# E-Fuse.net
KiCad netlist of a schematic drawn in Altium Designer
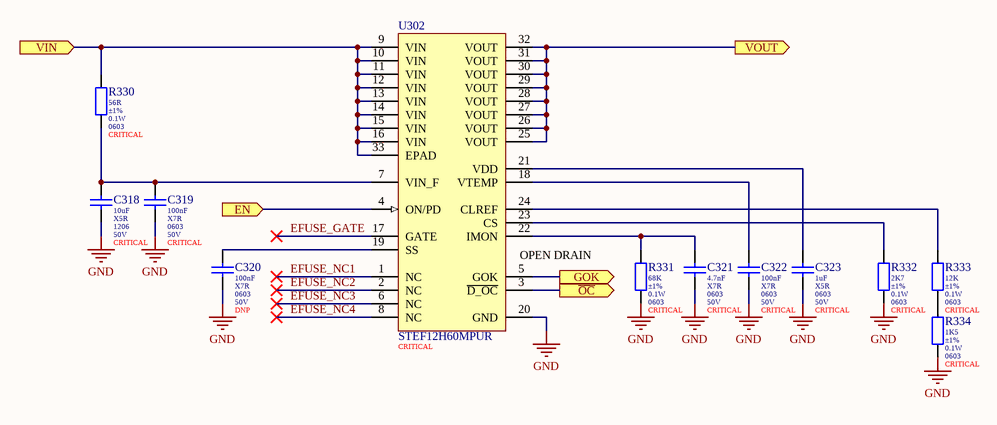
[diagram p0: E-Fuse.SchDoc]

(export (version "E")
  (design (tool "Eeschema 10.0.6"))
  (components
    (comp (ref "C318")
      (value "10uF")
      (footprint "1206_160_H (Samsumg) B")
      (description "MLCC 10uF 1206 50V X5R ±10%")
      (fields
        (field (name "DIELECTRIC") "X5R")
        (field (name "PACKAGE") "1206")
        (field (name "VOLTAGE") "50V")
        (field (name "POPULATE") "CRITICAL")
        (field (name "LCSC PART NUMBER") "C13585")
        (field (name "MANUFACTURER") "Samsung")
      )
      (libsource (lib "University of Cape Town") (part "Symbol"))
    )
    (comp (ref "C319")
      (value "100nF")
      (footprint "0603 (Yageo DA) B")
      (description "MLCC 100nF 50V 0603 X7R ±10%")
      (fields
        (field (name "DIELECTRIC") "X7R")
        (field (name "PACKAGE") "0603")
        (field (name "VOLTAGE") "50V")
        (field (name "POPULATE") "CRITICAL")
        (field (name "LCSC PART NUMBER") "C14663")
        (field (name "TOLERANCE") "±10%")
      )
      (libsource (lib "University of Cape Town") (part "Symbol"))
    )
    (comp (ref "C320")
      (value "100nF")
      (footprint "0603 (Yageo DA) B")
      (description "MLCC 100nF 50V 0603 X7R ±10%")
      (fields
        (field (name "DIELECTRIC") "X7R")
        (field (name "PACKAGE") "0603")
        (field (name "VOLTAGE") "50V")
        (field (name "POPULATE") "DNP")
        (field (name "LCSC PART NUMBER") "C14663")
        (field (name "TOLERANCE") "±10%")
      )
      (libsource (lib "University of Cape Town") (part "Symbol"))
    )
    (comp (ref "C321")
      (value "4.7nF")
      (footprint "0603_080 (Guandong) B")
      (description "MLCC 4.7nF 0603 50V X7R ±10%")
      (fields
        (field (name "DIELECTRIC") "X7R")
        (field (name "PACKAGE") "0603")
        (field (name "VOLTAGE") "50V")
        (field (name "POPULATE") "CRITICAL")
        (field (name "LCSC PART NUMBER") "C53987")
        (field (name "TOLERANCE") "±15%")
      )
      (libsource (lib "University of Cape Town") (part "Symbol"))
    )
    (comp (ref "C322")
      (value "100nF")
      (footprint "0603 (Yageo DA) B")
      (description "MLCC 100nF 50V 0603 X7R ±10%")
      (fields
        (field (name "DIELECTRIC") "X7R")
        (field (name "PACKAGE") "0603")
        (field (name "VOLTAGE") "50V")
        (field (name "POPULATE") "CRITICAL")
        (field (name "LCSC PART NUMBER") "C14663")
        (field (name "TOLERANCE") "±10%")
      )
      (libsource (lib "University of Cape Town") (part "Symbol"))
    )
    (comp (ref "C323")
      (value "1uF")
      (footprint "0603_080_8 (Samsung) B")
      (description "MLCC 1uF 0603 50V X5R ±10%")
      (fields
        (field (name "DIELECTRIC") "X5R")
        (field (name "PACKAGE") "0603")
        (field (name "VOLTAGE") "50V")
        (field (name "POPULATE") "CRITICAL")
        (field (name "TOLERANCE") "±10%")
        (field (name "MANUFACTURER") "Samsung")
      )
      (libsource (lib "University of Cape Town") (part "Symbol"))
    )
    (comp (ref "R330")
      (value "56R")
      (footprint "0603 (Uniroyal) B")
      (description "Resistor 56R 0603 ±1% Thick Film Uniroyal")
      (fields
        (field (name "TOLERANCE") "±1%")
        (field (name "POWER") "0.1W")
        (field (name "PACKAGE") "0603")
        (field (name "POPULATE") "CRITICAL")
        (field (name "MANUFACTURER") "Uniroyal")
        (field (name "LCSC PART NUMBER") "C25196")
      )
      (libsource (lib "University of Cape Town") (part "Chip Resistor"))
    )
    (comp (ref "R331")
      (value "68K")
      (footprint "0603 (Uniroyal) B")
      (description "Resistor 68K 0603 ±1% Thick Film Uniroyal")
      (fields
        (field (name "TOLERANCE") "±1%")
        (field (name "POWER") "0.1W")
        (field (name "PACKAGE") "0603")
        (field (name "POPULATE") "CRITICAL")
        (field (name "MANUFACTURER") "Uniroyal")
        (field (name "LCSC PART NUMBER") "C23231")
      )
      (libsource (lib "University of Cape Town") (part "Chip Resistor"))
    )
    (comp (ref "R332")
      (value "2K7")
      (footprint "0603 (Uniroyal) B")
      (description "Resistor 2K7 0603 ±1% Thick Film Uniroyal")
      (fields
        (field (name "TOLERANCE") "±1%")
        (field (name "POWER") "0.1W")
        (field (name "PACKAGE") "0603")
        (field (name "POPULATE") "CRITICAL")
        (field (name "LCSC PART NUMBER") "C13167")
        (field (name "MANUFACTURER") "Uniroyal")
      )
      (libsource (lib "University of Cape Town") (part "Chip Resistor"))
    )
    (comp (ref "R333")
      (value "12K")
      (footprint "0603 (Uniroyal) B")
      (description "Resistor 12K 0603 ±1% Thick Film Uniroyal")
      (fields
        (field (name "TOLERANCE") "±1%")
        (field (name "POWER") "0.1W")
        (field (name "PACKAGE") "0603")
        (field (name "POPULATE") "CRITICAL")
        (field (name "LCSC PART NUMBER") "C22790")
        (field (name "MANUFACTURER") "Uniroyal")
      )
      (libsource (lib "University of Cape Town") (part "Chip Resistor"))
    )
    (comp (ref "R334")
      (value "1K5")
      (footprint "0603 (Uniroyal) B")
      (description "Resistor 1K5 0603 ±1% Thick Film Uniroyal")
      (fields
        (field (name "TOLERANCE") "±1%")
        (field (name "POWER") "0.1W")
        (field (name "PACKAGE") "0603")
        (field (name "POPULATE") "CRITICAL")
        (field (name "MANUFACTURER") "Uniroyal")
        (field (name "LCSC PART NUMBER") "C22843")
      )
      (libsource (lib "University of Cape Town") (part "Chip Resistor"))
    )
    (comp (ref "U302")
      (value "STEF12H60MPUR")
      (footprint "QFN32 (STEF12H60) B")
      (description "Electronic Fuse 60A 8-15V QFN32 ST")
      (fields (field (name "PLACEMENT") "CRITICAL") (field (name "MANUFACTURER") "ST Microelectronics"))
      (libsource (lib "University of Cape Town") (part "STEF12H60"))
    )
  )
  (nets
    (net (code "1") (name "/EFUSE_GATE") (class "Default")
      (node (ref "U302") (pin "17") (pinfunction "GATE_17") (pintype "passive+no_connect"))
    )
    (net (code "2") (name "/EFUSE_NC1") (class "Default")
      (node (ref "U302") (pin "1") (pinfunction "NC_1") (pintype "passive+no_connect"))
    )
    (net (code "3") (name "/EFUSE_NC2") (class "Default")
      (node (ref "U302") (pin "2") (pinfunction "NC_2") (pintype "passive+no_connect"))
    )
    (net (code "4") (name "/EFUSE_NC3") (class "Default")
      (node (ref "U302") (pin "6") (pinfunction "NC_6") (pintype "passive+no_connect"))
    )
    (net (code "5") (name "/EFUSE_NC4") (class "Default")
      (node (ref "U302") (pin "8") (pinfunction "NC_8") (pintype "passive+no_connect"))
    )
    (net (code "6") (name "/EN") (class "Default")
      (node (ref "U302") (pin "4") (pinfunction "ON/PD_4") (pintype "input"))
    )
    (net (code "7") (name "/GOK") (class "Default")
      (node (ref "U302") (pin "5") (pinfunction "GOK_5") (pintype "open_collector"))
    )
    (net (code "8") (name "/OC") (class "Default")
      (node (ref "U302") (pin "3") (pinfunction "D_OC_3") (pintype "open_collector"))
    )
    (net (code "9") (name "/VIN") (class "Default")
      (node (ref "R330") (pin "1") (pinfunction "1_1") (pintype "passive"))
      (node (ref "U302") (pin "10") (pinfunction "VIN_10") (pintype "power_in"))
      (node (ref "U302") (pin "11") (pinfunction "VIN_11") (pintype "power_in"))
      (node (ref "U302") (pin "12") (pinfunction "VIN_12") (pintype "power_in"))
      (node (ref "U302") (pin "13") (pinfunction "VIN_13") (pintype "power_in"))
      (node (ref "U302") (pin "14") (pinfunction "VIN_14") (pintype "power_in"))
      (node (ref "U302") (pin "15") (pinfunction "VIN_15") (pintype "power_in"))
      (node (ref "U302") (pin "16") (pinfunction "VIN_16") (pintype "power_in"))
      (node (ref "U302") (pin "33") (pinfunction "EPAD_33") (pintype "power_in"))
      (node (ref "U302") (pin "9") (pinfunction "VIN_9") (pintype "power_in"))
    )
    (net (code "10") (name "/VOUT") (class "Default")
      (node (ref "U302") (pin "25") (pinfunction "VOUT_25") (pintype "power_in"))
      (node (ref "U302") (pin "26") (pinfunction "VOUT_26") (pintype "power_in"))
      (node (ref "U302") (pin "27") (pinfunction "VOUT_27") (pintype "power_in"))
      (node (ref "U302") (pin "28") (pinfunction "VOUT_28") (pintype "power_in"))
      (node (ref "U302") (pin "29") (pinfunction "VOUT_29") (pintype "power_in"))
      (node (ref "U302") (pin "30") (pinfunction "VOUT_30") (pintype "power_in"))
      (node (ref "U302") (pin "31") (pinfunction "VOUT_31") (pintype "power_in"))
      (node (ref "U302") (pin "32") (pinfunction "VOUT_32") (pintype "power_in"))
    )
    (net (code "11") (name "GND") (class "Default")
      (node (ref "C318") (pin "2") (pinfunction "2_2") (pintype "passive"))
      (node (ref "C319") (pin "2") (pinfunction "2_2") (pintype "passive"))
      (node (ref "C320") (pin "2") (pinfunction "2_2") (pintype "passive"))
      (node (ref "C321") (pin "2") (pinfunction "2_2") (pintype "passive"))
      (node (ref "C322") (pin "2") (pinfunction "2_2") (pintype "passive"))
      (node (ref "C323") (pin "2") (pinfunction "2_2") (pintype "passive"))
      (node (ref "R331") (pin "2") (pinfunction "2_2") (pintype "passive"))
      (node (ref "R332") (pin "2") (pinfunction "2_2") (pintype "passive"))
      (node (ref "R334") (pin "2") (pinfunction "2_2") (pintype "passive"))
      (node (ref "U302") (pin "20") (pinfunction "GND_20") (pintype "power_in"))
    )
    (net (code "12") (name "Net-(R333-Pad2)") (class "Default")
      (node (ref "R333") (pin "2") (pinfunction "2_2") (pintype "passive"))
      (node (ref "R334") (pin "1") (pinfunction "1_1") (pintype "passive"))
    )
    (net (code "13") (name "Net-(U302-CLREF)") (class "Default")
      (node (ref "R333") (pin "1") (pinfunction "1_1") (pintype "passive"))
      (node (ref "U302") (pin "24") (pinfunction "CLREF_24") (pintype "passive"))
    )
    (net (code "14") (name "Net-(U302-CS)") (class "Default")
      (node (ref "R332") (pin "1") (pinfunction "1_1") (pintype "passive"))
      (node (ref "U302") (pin "23") (pinfunction "CS_23") (pintype "passive"))
    )
    (net (code "15") (name "Net-(U302-IMON)") (class "Default")
      (node (ref "C321") (pin "1") (pinfunction "1_1") (pintype "passive"))
      (node (ref "R331") (pin "1") (pinfunction "1_1") (pintype "passive"))
      (node (ref "U302") (pin "22") (pinfunction "IMON_22") (pintype "passive"))
    )
    (net (code "16") (name "Net-(U302-SS)") (class "Default")
      (node (ref "C320") (pin "1") (pinfunction "1_1") (pintype "passive"))
      (node (ref "U302") (pin "19") (pinfunction "SS_19") (pintype "passive"))
    )
    (net (code "17") (name "Net-(U302-VDD)") (class "Default")
      (node (ref "C323") (pin "1") (pinfunction "1_1") (pintype "passive"))
      (node (ref "U302") (pin "21") (pinfunction "VDD_21") (pintype "power_in"))
    )
    (net (code "18") (name "Net-(U302-VIN_F)") (class "Default")
      (node (ref "C318") (pin "1") (pinfunction "1_1") (pintype "passive"))
      (node (ref "C319") (pin "1") (pinfunction "1_1") (pintype "passive"))
      (node (ref "R330") (pin "2") (pinfunction "2_2") (pintype "passive"))
      (node (ref "U302") (pin "7") (pinfunction "VIN_F_7") (pintype "power_in"))
    )
    (net (code "19") (name "Net-(U302-VTEMP)") (class "Default")
      (node (ref "C322") (pin "1") (pinfunction "1_1") (pintype "passive"))
      (node (ref "U302") (pin "18") (pinfunction "VTEMP_18") (pintype "open_emitter"))
    )
  )
)
